# lpf.net
KiCad netlist of a schematic drawn in Altium Designer
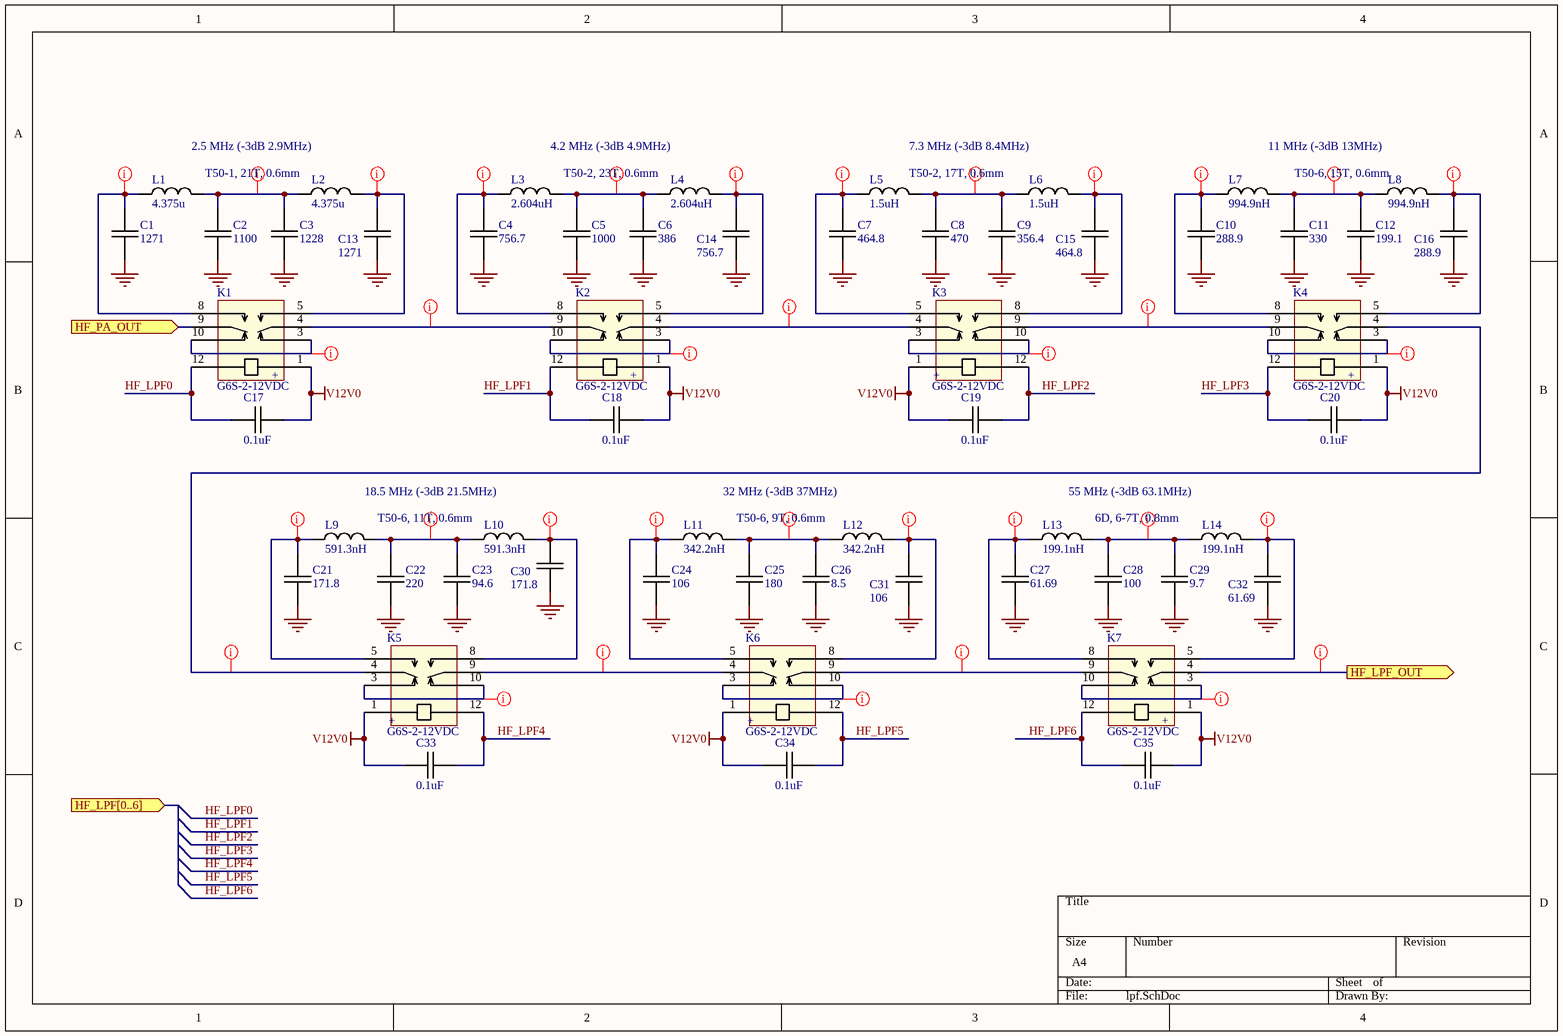
[diagram p0: lpf.SchDoc]

(export (version "E")
  (design (tool "Eeschema 10.0.6"))
  (components
    (comp (ref "C1")
      (value "1271")
      (footprint "CAPC3216X125N")
      (description "1206, NP0, 1kV")
      (libsource (lib "common-lib") (part "Cap1206"))
    )
    (comp (ref "C2")
      (value "1100")
      (footprint "CAPC3216X125N")
      (description "1206, NP0, 1kV")
      (libsource (lib "common-lib") (part "Cap1206"))
    )
    (comp (ref "C3")
      (value "1228")
      (footprint "CAPC3216X125N")
      (description "1206, NP0, 1kV")
      (libsource (lib "common-lib") (part "Cap1206"))
    )
    (comp (ref "C4")
      (value "756.7")
      (footprint "CAPC3216X125N")
      (description "1206, NP0, 1kV")
      (libsource (lib "common-lib") (part "Cap1206"))
    )
    (comp (ref "C5")
      (value "1000")
      (footprint "CAPC3216X125N")
      (description "1206, NP0, 1kV")
      (libsource (lib "common-lib") (part "Cap1206"))
    )
    (comp (ref "C6")
      (value "386")
      (footprint "CAPC3216X125N")
      (description "1206, NP0, 1kV")
      (libsource (lib "common-lib") (part "Cap1206"))
    )
    (comp (ref "C7")
      (value "464.8")
      (footprint "CAPC3216X125N")
      (description "1206, NP0, 1kV")
      (libsource (lib "common-lib") (part "Cap1206"))
    )
    (comp (ref "C8")
      (value "470")
      (footprint "CAPC3216X125N")
      (description "1206, NP0, 1kV")
      (libsource (lib "common-lib") (part "Cap1206"))
    )
    (comp (ref "C9")
      (value "356.4")
      (footprint "CAPC3216X125N")
      (description "1206, NP0, 1kV")
      (libsource (lib "common-lib") (part "Cap1206"))
    )
    (comp (ref "C10")
      (value "288.9")
      (footprint "CAPC3216X125N")
      (description "1206, NP0, 1kV")
      (libsource (lib "common-lib") (part "Cap1206"))
    )
    (comp (ref "C11")
      (value "330")
      (footprint "CAPC3216X125N")
      (description "1206, NP0, 1kV")
      (libsource (lib "common-lib") (part "Cap1206"))
    )
    (comp (ref "C12")
      (value "199.1")
      (footprint "CAPC3216X125N")
      (description "1206, NP0, 1kV")
      (libsource (lib "common-lib") (part "Cap1206"))
    )
    (comp (ref "C13")
      (value "1271")
      (footprint "CAPC3216X125N")
      (description "1206, NP0, 1kV")
      (libsource (lib "common-lib") (part "Cap1206"))
    )
    (comp (ref "C14")
      (value "756.7")
      (footprint "CAPC3216X125N")
      (description "1206, NP0, 1kV")
      (libsource (lib "common-lib") (part "Cap1206"))
    )
    (comp (ref "C15")
      (value "464.8")
      (footprint "CAPC3216X125N")
      (description "1206, NP0, 1kV")
      (libsource (lib "common-lib") (part "Cap1206"))
    )
    (comp (ref "C16")
      (value "288.9")
      (footprint "CAPC3216X125N")
      (description "1206, NP0, 1kV")
      (libsource (lib "common-lib") (part "Cap1206"))
    )
    (comp (ref "C17")
      (value "0.1uF")
      (footprint "CAPC2013X100N")
      (description "Capacitor 2x1.25 mm")
      (libsource (lib "common-lib") (part "Cap0805"))
    )
    (comp (ref "C18")
      (value "0.1uF")
      (footprint "CAPC2013X100N")
      (description "Capacitor 2x1.25 mm")
      (libsource (lib "common-lib") (part "Cap0805"))
    )
    (comp (ref "C19")
      (value "0.1uF")
      (footprint "CAPC2013X100N")
      (description "Capacitor 2x1.25 mm")
      (libsource (lib "common-lib") (part "Cap0805"))
    )
    (comp (ref "C20")
      (value "0.1uF")
      (footprint "CAPC2013X100N")
      (description "Capacitor 2x1.25 mm")
      (libsource (lib "common-lib") (part "Cap0805"))
    )
    (comp (ref "C21")
      (value "171.8")
      (footprint "CAPC3216X125N")
      (description "1206, NP0, 1kV")
      (libsource (lib "common-lib") (part "Cap1206"))
    )
    (comp (ref "C22")
      (value "220")
      (footprint "CAPC3216X125N")
      (description "1206, NP0, 1kV")
      (libsource (lib "common-lib") (part "Cap1206"))
    )
    (comp (ref "C23")
      (value "94.6")
      (footprint "CAPC3216X125N")
      (description "1206, NP0, 1kV")
      (libsource (lib "common-lib") (part "Cap1206"))
    )
    (comp (ref "C24")
      (value "106")
      (footprint "CAPC3216X125N")
      (description "1206, NP0, 1kV")
      (libsource (lib "common-lib") (part "Cap1206"))
    )
    (comp (ref "C25")
      (value "180")
      (footprint "CAPC3216X125N")
      (description "1206, NP0, 1kV")
      (libsource (lib "common-lib") (part "Cap1206"))
    )
    (comp (ref "C26")
      (value "8.5")
      (footprint "CAPC3216X125N")
      (description "1206, NP0, 1kV")
      (libsource (lib "common-lib") (part "Cap1206"))
    )
    (comp (ref "C27")
      (value "61.69")
      (footprint "CAPC3216X125N")
      (description "1206, NP0, 1kV")
      (libsource (lib "common-lib") (part "Cap1206"))
    )
    (comp (ref "C28")
      (value "100")
      (footprint "CAPC3216X125N")
      (description "1206, NP0, 1kV")
      (libsource (lib "common-lib") (part "Cap1206"))
    )
    (comp (ref "C29")
      (value "9.7")
      (footprint "CAPC3216X125N")
      (description "1206, NP0, 1kV")
      (libsource (lib "common-lib") (part "Cap1206"))
    )
    (comp (ref "C30")
      (value "171.8")
      (footprint "CAPC3216X125N")
      (description "1206, NP0, 1kV")
      (libsource (lib "common-lib") (part "Cap1206"))
    )
    (comp (ref "C31")
      (value "106")
      (footprint "CAPC3216X125N")
      (description "1206, NP0, 1kV")
      (libsource (lib "common-lib") (part "Cap1206"))
    )
    (comp (ref "C32")
      (value "61.69")
      (footprint "CAPC3216X125N")
      (description "1206, NP0, 1kV")
      (libsource (lib "common-lib") (part "Cap1206"))
    )
    (comp (ref "C33")
      (value "0.1uF")
      (footprint "CAPC2013X100N")
      (description "Capacitor 2x1.25 mm")
      (libsource (lib "common-lib") (part "Cap0805"))
    )
    (comp (ref "C34")
      (value "0.1uF")
      (footprint "CAPC2013X100N")
      (description "Capacitor 2x1.25 mm")
      (libsource (lib "common-lib") (part "Cap0805"))
    )
    (comp (ref "C35")
      (value "0.1uF")
      (footprint "CAPC2013X100N")
      (description "Capacitor 2x1.25 mm")
      (libsource (lib "common-lib") (part "Cap0805"))
    )
    (comp (ref "K1")
      (value "G6S-2-12VDC")
      (footprint "G6S-2")
      (description "Compact, Industry-Standard 2-pole relay")
      (libsource (lib "") (part "G6S-2-12VDC_1"))
    )
    (comp (ref "K2")
      (value "G6S-2-12VDC")
      (footprint "G6S-2")
      (description "Compact, Industry-Standard 2-pole relay")
      (libsource (lib "") (part "G6S-2-12VDC_1"))
    )
    (comp (ref "K3")
      (value "G6S-2-12VDC")
      (footprint "G6S-2")
      (description "Compact, Industry-Standard 2-pole relay")
      (libsource (lib "PALib") (part "G6S-2-12VDC"))
    )
    (comp (ref "K4")
      (value "G6S-2-12VDC")
      (footprint "G6S-2")
      (description "Compact, Industry-Standard 2-pole relay")
      (libsource (lib "") (part "G6S-2-12VDC_1"))
    )
    (comp (ref "K5")
      (value "G6S-2-12VDC")
      (footprint "G6S-2")
      (description "Compact, Industry-Standard 2-pole relay")
      (libsource (lib "PALib") (part "G6S-2-12VDC"))
    )
    (comp (ref "K6")
      (value "G6S-2-12VDC")
      (footprint "G6S-2")
      (description "Compact, Industry-Standard 2-pole relay")
      (libsource (lib "PALib") (part "G6S-2-12VDC"))
    )
    (comp (ref "K7")
      (value "G6S-2-12VDC")
      (footprint "G6S-2")
      (description "Compact, Industry-Standard 2-pole relay")
      (libsource (lib "") (part "G6S-2-12VDC_1"))
    )
    (comp (ref "L1")
      (value "4.375u")
      (footprint "T50-2")
      (description "T50-1")
      (libsource (lib "PALib") (part "Inductor"))
    )
    (comp (ref "L2")
      (value "4.375u")
      (footprint "T50-2")
      (description "T50-1")
      (libsource (lib "PALib") (part "Inductor"))
    )
    (comp (ref "L3")
      (value "2.604uH")
      (footprint "T50-2")
      (description "T50-2")
      (libsource (lib "") (part "Inductor_1"))
    )
    (comp (ref "L4")
      (value "2.604uH")
      (footprint "T50-2")
      (description "T50-2")
      (libsource (lib "") (part "Inductor_1"))
    )
    (comp (ref "L5")
      (value "1.5uH")
      (footprint "T50-6")
      (description "T50-2")
      (libsource (lib "") (part "Inductor_1"))
    )
    (comp (ref "L6")
      (value "1.5uH")
      (footprint "T50-6")
      (description "T50-2")
      (libsource (lib "") (part "Inductor_1"))
    )
    (comp (ref "L7")
      (value "994.9nH")
      (footprint "T50-6")
      (description "T50-6")
      (libsource (lib "") (part "Inductor_1"))
    )
    (comp (ref "L8")
      (value "994.9nH")
      (footprint "T50-6")
      (description "T50-6")
      (libsource (lib "") (part "Inductor_1"))
    )
    (comp (ref "L9")
      (value "591.3nH")
      (footprint "T50-6")
      (description "T50-6")
      (libsource (lib "PALib") (part "Inductor"))
    )
    (comp (ref "L10")
      (value "591.3nH")
      (footprint "T50-6")
      (description "T50-6")
      (libsource (lib "") (part "Inductor_1"))
    )
    (comp (ref "L11")
      (value "342.2nH")
      (footprint "T50-6")
      (description "T50-6")
      (libsource (lib "") (part "Inductor_1"))
    )
    (comp (ref "L12")
      (value "342.2nH")
      (footprint "T50-6")
      (description "T50-6")
      (libsource (lib "") (part "Inductor_1"))
    )
    (comp (ref "L13")
      (value "199.1nH")
      (footprint "T50-6")
      (description "T50-6")
      (libsource (lib "") (part "Inductor_1"))
    )
    (comp (ref "L14")
      (value "199.1nH")
      (footprint "T50-6")
      (description "T50-6")
      (libsource (lib "") (part "Inductor_1"))
    )
  )
  (nets
    (net (code "1") (name "/HF_LPF0") (class "Default")
      (node (ref "C17") (pin "2") (pintype "passive"))
      (node (ref "K1") (pin "12") (pintype "passive"))
    )
    (net (code "2") (name "/HF_LPF1") (class "Default")
      (node (ref "C18") (pin "2") (pintype "passive"))
      (node (ref "K2") (pin "12") (pintype "passive"))
    )
    (net (code "3") (name "/HF_LPF2") (class "Default")
      (node (ref "C19") (pin "1") (pintype "passive"))
      (node (ref "K3") (pin "12") (pintype "passive"))
    )
    (net (code "4") (name "/HF_LPF3") (class "Default")
      (node (ref "C20") (pin "2") (pintype "passive"))
      (node (ref "K4") (pin "12") (pintype "passive"))
    )
    (net (code "5") (name "/HF_LPF4") (class "Default")
      (node (ref "C33") (pin "1") (pintype "passive"))
      (node (ref "K5") (pin "12") (pintype "passive"))
    )
    (net (code "6") (name "/HF_LPF5") (class "Default")
      (node (ref "C34") (pin "1") (pintype "passive"))
      (node (ref "K6") (pin "12") (pintype "passive"))
    )
    (net (code "7") (name "/HF_LPF6") (class "Default")
      (node (ref "C35") (pin "2") (pintype "passive"))
      (node (ref "K7") (pin "12") (pintype "passive"))
    )
    (net (code "9") (name "/HF_LPF_OUT") (class "Default") (node (ref "K7") (pin "4") (pintype "passive")))
    (net (code "10") (name "/HF_PA_OUT") (class "Default") (node (ref "K1") (pin "9") (pintype "passive")))
    (net (code "11") (name "GND") (class "Default")
      (node (ref "C1") (pin "1") (pintype "passive"))
      (node (ref "C10") (pin "1") (pintype "passive"))
      (node (ref "C11") (pin "1") (pintype "passive"))
      (node (ref "C12") (pin "1") (pintype "passive"))
      (node (ref "C13") (pin "1") (pintype "passive"))
      (node (ref "C14") (pin "1") (pintype "passive"))
      (node (ref "C15") (pin "1") (pintype "passive"))
      (node (ref "C16") (pin "1") (pintype "passive"))
      (node (ref "C2") (pin "1") (pintype "passive"))
      (node (ref "C21") (pin "1") (pintype "passive"))
      (node (ref "C22") (pin "1") (pintype "passive"))
      (node (ref "C23") (pin "1") (pintype "passive"))
      (node (ref "C24") (pin "1") (pintype "passive"))
      (node (ref "C25") (pin "1") (pintype "passive"))
      (node (ref "C26") (pin "1") (pintype "passive"))
      (node (ref "C27") (pin "1") (pintype "passive"))
      (node (ref "C28") (pin "1") (pintype "passive"))
      (node (ref "C29") (pin "1") (pintype "passive"))
      (node (ref "C3") (pin "1") (pintype "passive"))
      (node (ref "C30") (pin "1") (pintype "passive"))
      (node (ref "C31") (pin "1") (pintype "passive"))
      (node (ref "C32") (pin "1") (pintype "passive"))
      (node (ref "C4") (pin "1") (pintype "passive"))
      (node (ref "C5") (pin "1") (pintype "passive"))
      (node (ref "C6") (pin "1") (pintype "passive"))
      (node (ref "C7") (pin "1") (pintype "passive"))
      (node (ref "C8") (pin "1") (pintype "passive"))
      (node (ref "C9") (pin "1") (pintype "passive"))
    )
    (net (code "12") (name "Net-(C1-Pad2)") (class "Default")
      (node (ref "C1") (pin "2") (pintype "passive"))
      (node (ref "K1") (pin "8") (pintype "passive"))
      (node (ref "L1") (pin "1") (pintype "passive"))
    )
    (net (code "13") (name "Net-(C2-Pad2)") (class "Default")
      (node (ref "C2") (pin "2") (pintype "passive"))
      (node (ref "C3") (pin "2") (pintype "passive"))
      (node (ref "L1") (pin "2") (pintype "passive"))
      (node (ref "L2") (pin "1") (pintype "passive"))
    )
    (net (code "14") (name "Net-(C4-Pad2)") (class "Default")
      (node (ref "C4") (pin "2") (pintype "passive"))
      (node (ref "K2") (pin "8") (pintype "passive"))
      (node (ref "L3") (pin "1") (pintype "passive"))
    )
    (net (code "15") (name "Net-(C5-Pad2)") (class "Default")
      (node (ref "C5") (pin "2") (pintype "passive"))
      (node (ref "C6") (pin "2") (pintype "passive"))
      (node (ref "L3") (pin "2") (pintype "passive"))
      (node (ref "L4") (pin "1") (pintype "passive"))
    )
    (net (code "16") (name "Net-(C7-Pad2)") (class "Default")
      (node (ref "C7") (pin "2") (pintype "passive"))
      (node (ref "K3") (pin "5") (pintype "passive"))
      (node (ref "L5") (pin "1") (pintype "passive"))
    )
    (net (code "17") (name "Net-(C8-Pad2)") (class "Default")
      (node (ref "C8") (pin "2") (pintype "passive"))
      (node (ref "C9") (pin "2") (pintype "passive"))
      (node (ref "L5") (pin "2") (pintype "passive"))
      (node (ref "L6") (pin "1") (pintype "passive"))
    )
    (net (code "18") (name "Net-(C10-Pad2)") (class "Default")
      (node (ref "C10") (pin "2") (pintype "passive"))
      (node (ref "K4") (pin "8") (pintype "passive"))
      (node (ref "L7") (pin "1") (pintype "passive"))
    )
    (net (code "19") (name "Net-(C11-Pad2)") (class "Default")
      (node (ref "C11") (pin "2") (pintype "passive"))
      (node (ref "C12") (pin "2") (pintype "passive"))
      (node (ref "L7") (pin "2") (pintype "passive"))
      (node (ref "L8") (pin "1") (pintype "passive"))
    )
    (net (code "20") (name "Net-(C13-Pad2)") (class "Default")
      (node (ref "C13") (pin "2") (pintype "passive"))
      (node (ref "K1") (pin "5") (pintype "passive"))
      (node (ref "L2") (pin "2") (pintype "passive"))
    )
    (net (code "21") (name "Net-(C14-Pad2)") (class "Default")
      (node (ref "C14") (pin "2") (pintype "passive"))
      (node (ref "K2") (pin "5") (pintype "passive"))
      (node (ref "L4") (pin "2") (pintype "passive"))
    )
    (net (code "22") (name "Net-(C15-Pad2)") (class "Default")
      (node (ref "C15") (pin "2") (pintype "passive"))
      (node (ref "K3") (pin "8") (pintype "passive"))
      (node (ref "L6") (pin "2") (pintype "passive"))
    )
    (net (code "23") (name "Net-(C16-Pad2)") (class "Default")
      (node (ref "C16") (pin "2") (pintype "passive"))
      (node (ref "K4") (pin "5") (pintype "passive"))
      (node (ref "L8") (pin "2") (pintype "passive"))
    )
    (net (code "24") (name "Net-(C21-Pad2)") (class "Default")
      (node (ref "C21") (pin "2") (pintype "passive"))
      (node (ref "K5") (pin "5") (pintype "passive"))
      (node (ref "L9") (pin "1") (pintype "passive"))
    )
    (net (code "25") (name "Net-(C22-Pad2)") (class "Default")
      (node (ref "C22") (pin "2") (pintype "passive"))
      (node (ref "C23") (pin "2") (pintype "passive"))
      (node (ref "L10") (pin "1") (pintype "passive"))
      (node (ref "L9") (pin "2") (pintype "passive"))
    )
    (net (code "26") (name "Net-(C24-Pad2)") (class "Default")
      (node (ref "C24") (pin "2") (pintype "passive"))
      (node (ref "K6") (pin "5") (pintype "passive"))
      (node (ref "L11") (pin "1") (pintype "passive"))
    )
    (net (code "27") (name "Net-(C25-Pad2)") (class "Default")
      (node (ref "C25") (pin "2") (pintype "passive"))
      (node (ref "C26") (pin "2") (pintype "passive"))
      (node (ref "L11") (pin "2") (pintype "passive"))
      (node (ref "L12") (pin "1") (pintype "passive"))
    )
    (net (code "28") (name "Net-(C27-Pad2)") (class "Default")
      (node (ref "C27") (pin "2") (pintype "passive"))
      (node (ref "K7") (pin "8") (pintype "passive"))
      (node (ref "L13") (pin "1") (pintype "passive"))
    )
    (net (code "29") (name "Net-(C28-Pad2)") (class "Default")
      (node (ref "C28") (pin "2") (pintype "passive"))
      (node (ref "C29") (pin "2") (pintype "passive"))
      (node (ref "L13") (pin "2") (pintype "passive"))
      (node (ref "L14") (pin "1") (pintype "passive"))
    )
    (net (code "30") (name "Net-(C30-Pad2)") (class "Default")
      (node (ref "C30") (pin "2") (pintype "passive"))
      (node (ref "K5") (pin "8") (pintype "passive"))
      (node (ref "L10") (pin "2") (pintype "passive"))
    )
    (net (code "31") (name "Net-(C31-Pad2)") (class "Default")
      (node (ref "C31") (pin "2") (pintype "passive"))
      (node (ref "K6") (pin "8") (pintype "passive"))
      (node (ref "L12") (pin "2") (pintype "passive"))
    )
    (net (code "32") (name "Net-(C32-Pad2)") (class "Default")
      (node (ref "C32") (pin "2") (pintype "passive"))
      (node (ref "K7") (pin "5") (pintype "passive"))
      (node (ref "L14") (pin "2") (pintype "passive"))
    )
    (net (code "33") (name "Net-(K1-Pad4)") (class "Default")
      (node (ref "K1") (pin "4") (pintype "passive"))
      (node (ref "K2") (pin "9") (pintype "passive"))
    )
    (net (code "34") (name "Net-(K1-Pad10)") (class "Default")
      (node (ref "K1") (pin "10") (pintype "passive"))
      (node (ref "K1") (pin "3") (pintype "passive"))
    )
    (net (code "35") (name "Net-(K2-Pad4)") (class "Default")
      (node (ref "K2") (pin "4") (pintype "passive"))
      (node (ref "K3") (pin "4") (pintype "passive"))
    )
    (net (code "36") (name "Net-(K2-Pad10)") (class "Default")
      (node (ref "K2") (pin "10") (pintype "passive"))
      (node (ref "K2") (pin "3") (pintype "passive"))
    )
    (net (code "37") (name "Net-(K3-Pad9)") (class "Default")
      (node (ref "K3") (pin "9") (pintype "passive"))
      (node (ref "K4") (pin "9") (pintype "passive"))
    )
    (net (code "38") (name "Net-(K3-Pad10)") (class "Default")
      (node (ref "K3") (pin "10") (pintype "passive"))
      (node (ref "K3") (pin "3") (pintype "passive"))
    )
    (net (code "39") (name "Net-(K4-Pad4)") (class "Default")
      (node (ref "K4") (pin "4") (pintype "passive"))
      (node (ref "K5") (pin "4") (pintype "passive"))
    )
    (net (code "40") (name "Net-(K4-Pad10)") (class "Default")
      (node (ref "K4") (pin "10") (pintype "passive"))
      (node (ref "K4") (pin "3") (pintype "passive"))
    )
    (net (code "41") (name "Net-(K5-Pad9)") (class "Default")
      (node (ref "K5") (pin "9") (pintype "passive"))
      (node (ref "K6") (pin "4") (pintype "passive"))
    )
    (net (code "42") (name "Net-(K5-Pad10)") (class "Default")
      (node (ref "K5") (pin "10") (pintype "passive"))
      (node (ref "K5") (pin "3") (pintype "passive"))
    )
    (net (code "43") (name "Net-(K6-Pad9)") (class "Default")
      (node (ref "K6") (pin "9") (pintype "passive"))
      (node (ref "K7") (pin "9") (pintype "passive"))
    )
    (net (code "44") (name "Net-(K6-Pad10)") (class "Default")
      (node (ref "K6") (pin "10") (pintype "passive"))
      (node (ref "K6") (pin "3") (pintype "passive"))
    )
    (net (code "45") (name "Net-(K7-Pad10)") (class "Default")
      (node (ref "K7") (pin "10") (pintype "passive"))
      (node (ref "K7") (pin "3") (pintype "passive"))
    )
    (net (code "46") (name "V12V0") (class "Default")
      (node (ref "C17") (pin "1") (pintype "passive"))
      (node (ref "C18") (pin "1") (pintype "passive"))
      (node (ref "C19") (pin "2") (pintype "passive"))
      (node (ref "C20") (pin "1") (pintype "passive"))
      (node (ref "C33") (pin "2") (pintype "passive"))
      (node (ref "C34") (pin "2") (pintype "passive"))
      (node (ref "C35") (pin "1") (pintype "passive"))
      (node (ref "K1") (pin "1") (pintype "passive"))
      (node (ref "K2") (pin "1") (pintype "passive"))
      (node (ref "K3") (pin "1") (pintype "passive"))
      (node (ref "K4") (pin "1") (pintype "passive"))
      (node (ref "K5") (pin "1") (pintype "passive"))
      (node (ref "K6") (pin "1") (pintype "passive"))
      (node (ref "K7") (pin "1") (pintype "passive"))
    )
  )
)
